# Sheet1.net
KiCad netlist of a schematic drawn in Altium Designer
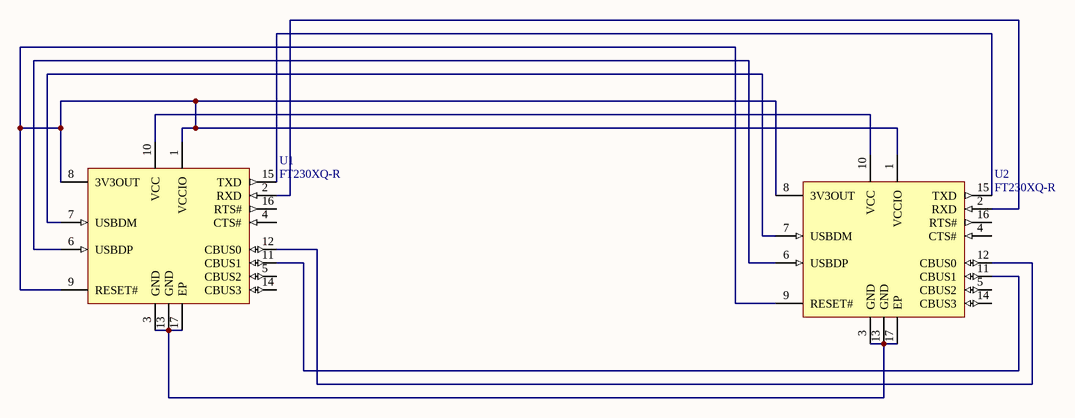
[diagram p0: Sheet1.SchDoc]

(export (version "E")
  (design (tool "Eeschema 10.0.6"))
  (components
    (comp (ref "U1")
      (value "FT230XQ-R")
      (footprint "QFN-16")
      (fields (field (name "MANUFACTURER") "FTDI"))
      (libsource (lib "CarlLibrary") (part "FT230XQ-R"))
    )
    (comp (ref "U2")
      (value "FT230XQ-R")
      (footprint "QFN-16")
      (fields (field (name "MANUFACTURER") "FTDI"))
      (libsource (lib "CarlLibrary") (part "FT230XQ-R"))
    )
  )
  (nets
    (net (code "1") (name "Net-(U1-3V3OUT)") (class "Default")
      (node (ref "U1") (pin "1") (pinfunction "VCCIO_1") (pintype "power_in"))
      (node (ref "U1") (pin "8") (pinfunction "3V3OUT_8") (pintype "power_in"))
      (node (ref "U1") (pin "9") (pinfunction "RESET#_9") (pintype "passive"))
      (node (ref "U2") (pin "1") (pinfunction "VCCIO_1") (pintype "power_in"))
      (node (ref "U2") (pin "8") (pinfunction "3V3OUT_8") (pintype "power_in"))
      (node (ref "U2") (pin "9") (pinfunction "RESET#_9") (pintype "passive"))
    )
    (net (code "2") (name "Net-(U1-CBUS0)") (class "Default")
      (node (ref "U1") (pin "12") (pinfunction "CBUS0_12") (pintype "bidirectional"))
      (node (ref "U2") (pin "12") (pinfunction "CBUS0_12") (pintype "bidirectional"))
    )
    (net (code "3") (name "Net-(U1-CBUS1)") (class "Default")
      (node (ref "U1") (pin "11") (pinfunction "CBUS1_11") (pintype "bidirectional"))
      (node (ref "U2") (pin "11") (pinfunction "CBUS1_11") (pintype "bidirectional"))
    )
    (net (code "4") (name "Net-(U1-EP)") (class "Default")
      (node (ref "U1") (pin "13") (pinfunction "GND_13") (pintype "power_in"))
      (node (ref "U1") (pin "17") (pinfunction "EP_17") (pintype "power_in"))
      (node (ref "U1") (pin "3") (pinfunction "GND_3") (pintype "power_in"))
      (node (ref "U2") (pin "13") (pinfunction "GND_13") (pintype "power_in"))
      (node (ref "U2") (pin "17") (pinfunction "EP_17") (pintype "power_in"))
      (node (ref "U2") (pin "3") (pinfunction "GND_3") (pintype "power_in"))
    )
    (net (code "5") (name "Net-(U1-RXD)") (class "Default")
      (node (ref "U1") (pin "2") (pinfunction "RXD_2") (pintype "input"))
      (node (ref "U2") (pin "2") (pinfunction "RXD_2") (pintype "input"))
    )
    (net (code "6") (name "Net-(U1-TXD)") (class "Default")
      (node (ref "U1") (pin "15") (pinfunction "TXD_15") (pintype "output"))
      (node (ref "U2") (pin "15") (pinfunction "TXD_15") (pintype "output"))
    )
    (net (code "7") (name "Net-(U1-USBDM)") (class "Default")
      (node (ref "U1") (pin "7") (pinfunction "USBDM_7") (pintype "input"))
      (node (ref "U2") (pin "7") (pinfunction "USBDM_7") (pintype "input"))
    )
    (net (code "8") (name "Net-(U1-USBDP)") (class "Default")
      (node (ref "U1") (pin "6") (pinfunction "USBDP_6") (pintype "input"))
      (node (ref "U2") (pin "6") (pinfunction "USBDP_6") (pintype "input"))
    )
    (net (code "9") (name "Net-(U1-VCC)") (class "Default")
      (node (ref "U1") (pin "10") (pinfunction "VCC_10") (pintype "power_in"))
      (node (ref "U2") (pin "10") (pinfunction "VCC_10") (pintype "power_in"))
    )
    (net (code "10") (name "unconnected-(U1-CBUS2-Pad5)") (class "Default")
      (node (ref "U1") (pin "5") (pinfunction "CBUS2_5") (pintype "bidirectional"))
    )
    (net (code "11") (name "unconnected-(U1-CBUS3-Pad14)") (class "Default")
      (node (ref "U1") (pin "14") (pinfunction "CBUS3_14") (pintype "bidirectional"))
    )
    (net (code "12") (name "unconnected-(U1-CTS#-Pad4)") (class "Default")
      (node (ref "U1") (pin "4") (pinfunction "CTS#_4") (pintype "input"))
    )
    (net (code "13") (name "unconnected-(U1-RTS#-Pad16)") (class "Default")
      (node (ref "U1") (pin "16") (pinfunction "RTS#_16") (pintype "output"))
    )
    (net (code "14") (name "unconnected-(U2-CBUS2-Pad5)") (class "Default")
      (node (ref "U2") (pin "5") (pinfunction "CBUS2_5") (pintype "bidirectional"))
    )
    (net (code "15") (name "unconnected-(U2-CBUS3-Pad14)") (class "Default")
      (node (ref "U2") (pin "14") (pinfunction "CBUS3_14") (pintype "bidirectional"))
    )
    (net (code "16") (name "unconnected-(U2-CTS#-Pad4)") (class "Default")
      (node (ref "U2") (pin "4") (pinfunction "CTS#_4") (pintype "input"))
    )
    (net (code "17") (name "unconnected-(U2-RTS#-Pad16)") (class "Default")
      (node (ref "U2") (pin "16") (pinfunction "RTS#_16") (pintype "output"))
    )
  )
)
